# SparkFun_Beefcake_Relay_Control_Kit.net
KiCad netlist of a schematic drawn in EAGLE
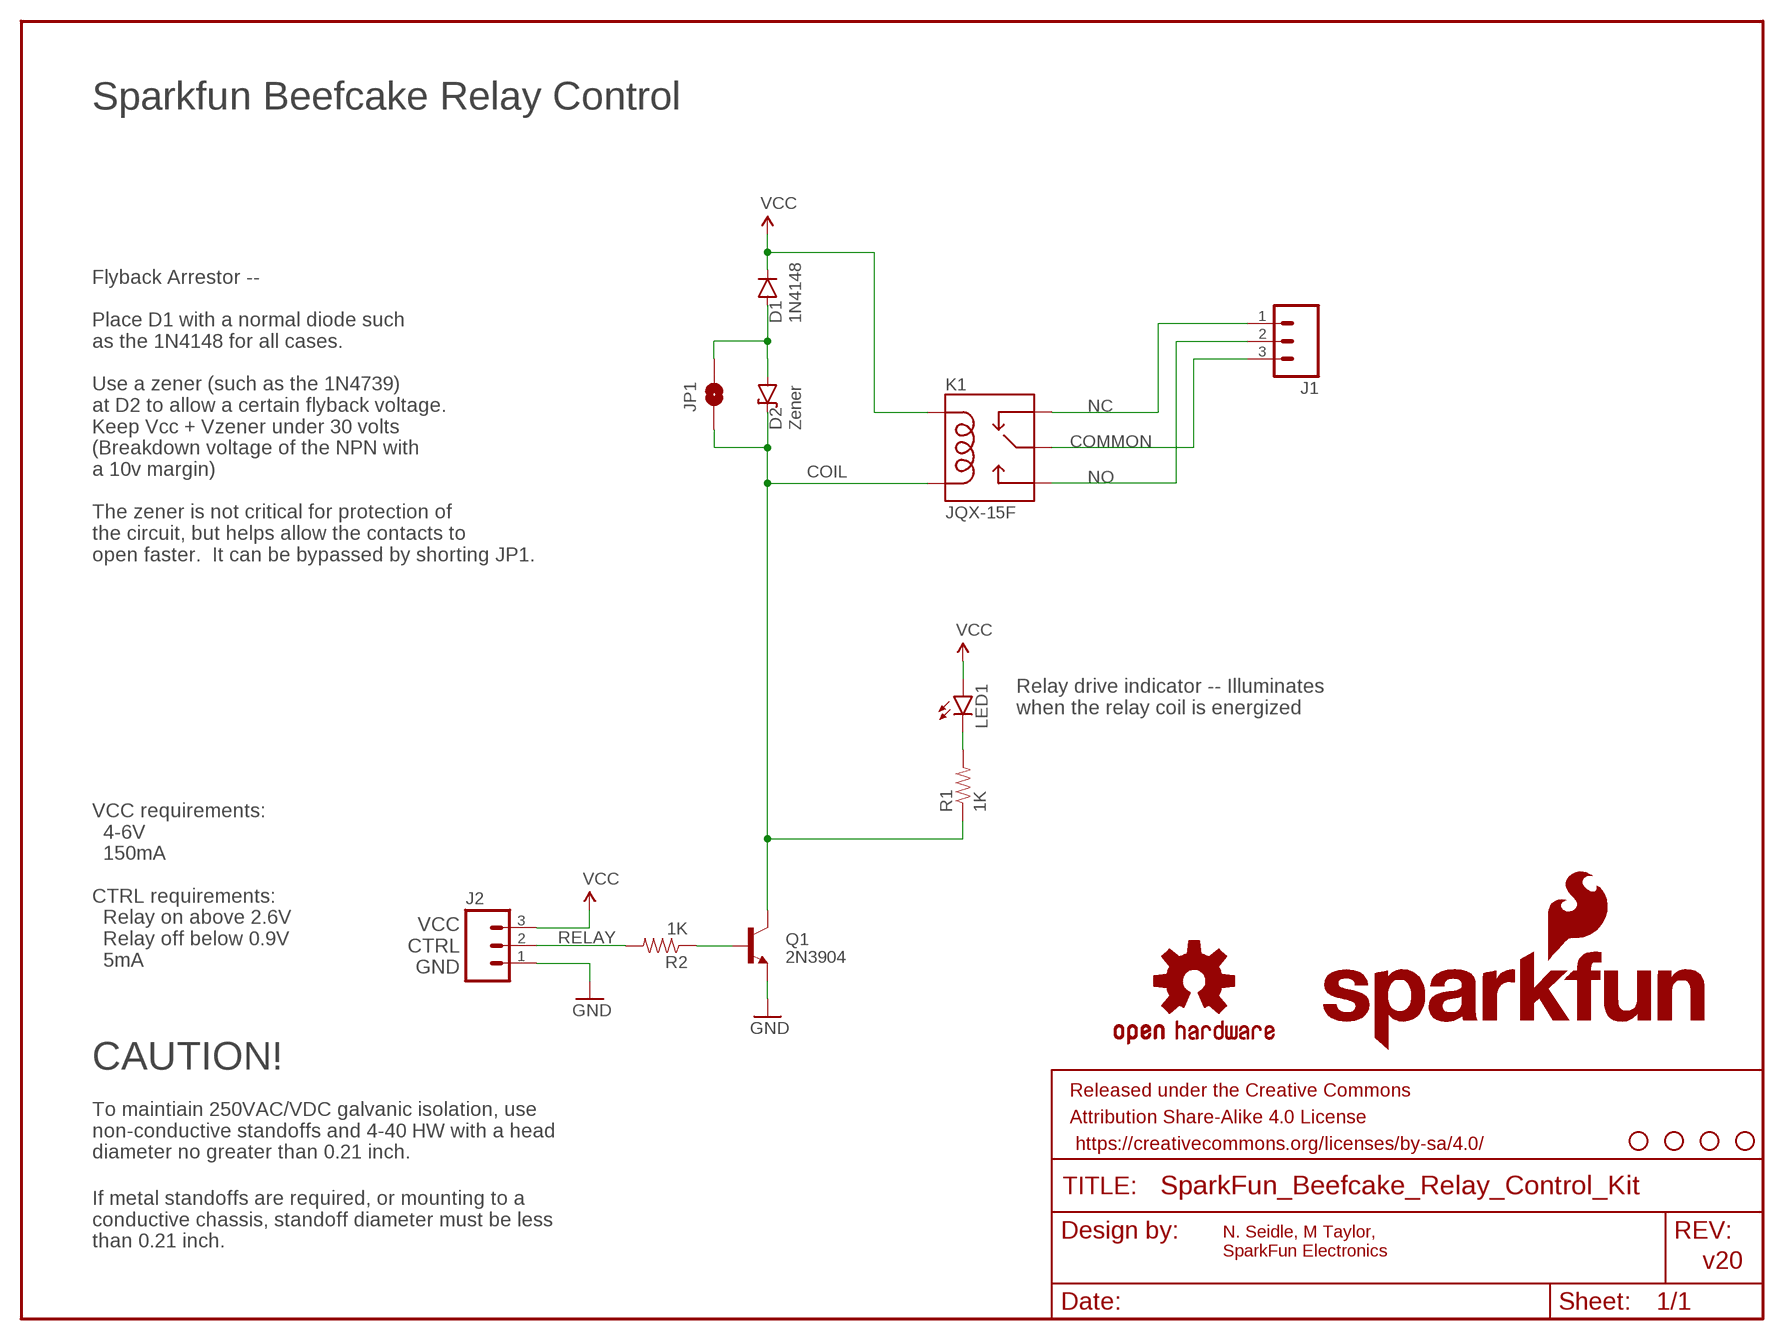
[diagram p0: schematic, sheet 1]

(export (version "E")
  (design (tool "Eeschema 10.0.6"))
  (components
    (comp (ref "D1")
      (value "1N4148")
      (footprint "eagle-import:DIODE-1N4148-KIT")
      (libsource (lib "eagle-import") (part "DIODEKIT"))
    )
    (comp (ref "D2")
      (value "Zener")
      (footprint "eagle-import:DIODE-1N4148-KIT")
      (libsource (lib "eagle-import") (part "DIODE-ZENER"))
    )
    (comp (ref "FRAME2")
      (value "FRAME-LETTER")
      (footprint "eagle-import:CREATIVE_COMMONS")
      (libsource (lib "eagle-import") (part "FRAME-LETTER"))
    )
    (comp (ref "J1")
      (value "M03-SCREW-5MM")
      (footprint "eagle-import:SCREWTERMINAL-5MM-3")
      (libsource (lib "eagle-import") (part "M03-SCREW-5MM"))
    )
    (comp (ref "J2")
      (value "M03SCREW")
      (footprint "eagle-import:SCREWTERMINAL-3.5MM-3")
      (libsource (lib "eagle-import") (part "M03SCREW"))
    )
    (comp (ref "JP1")
      (value "JUMPER-PAD-2-NOYES_SILK")
      (footprint "eagle-import:PAD-JUMPER-2-NO_YES_SILK")
      (libsource (lib "eagle-import") (part "JUMPER-PAD-2-NOYES_SILK"))
    )
    (comp (ref "K1")
      (value "JQX-15F")
      (footprint "eagle-import:RELAY-T90")
      (libsource (lib "eagle-import") (part "RELAYPTH5"))
    )
    (comp (ref "LED1")
      (value "LED5MM-KIT")
      (footprint "eagle-import:LED5MM-KIT")
      (fields (field (name "PROD_ID") "DIO-09529"))
      (libsource (lib "eagle-import") (part "LED5MM-KIT"))
    )
    (comp (ref "LOGO1")
      (value "SFE_LOGO_NAME_FLAME.1_INCH")
      (footprint "eagle-import:SFE_LOGO_NAME_FLAME_.1")
      (libsource (lib "eagle-import") (part "SFE_LOGO_NAME_FLAME.1_INCH"))
    )
    (comp (ref "Q1")
      (value "2N3904")
      (footprint "eagle-import:TO-92-EZ")
      (libsource (lib "eagle-import") (part "TRANSISTOR_NPN2N3904-EZ"))
    )
    (comp (ref "R1")
      (value "1K")
      (footprint "eagle-import:AXIAL-0.3EZ")
      (libsource (lib "eagle-import") (part "1KOHM-1/4W-1%(PTH)HORIZ-KIT"))
    )
    (comp (ref "R2")
      (value "1K")
      (footprint "eagle-import:AXIAL-0.3EZ")
      (libsource (lib "eagle-import") (part "1KOHM-1/4W-1%(PTH)HORIZ-KIT"))
    )
    (comp (ref "U$3")
      (value "STAND-OFF")
      (footprint "eagle-import:STAND-OFF")
      (libsource (lib "eagle-import") (part "STAND-OFF"))
    )
    (comp (ref "U$4")
      (value "STAND-OFF")
      (footprint "eagle-import:STAND-OFF")
      (libsource (lib "eagle-import") (part "STAND-OFF"))
    )
    (comp (ref "U$5")
      (value "STAND-OFF")
      (footprint "eagle-import:STAND-OFF")
      (libsource (lib "eagle-import") (part "STAND-OFF"))
    )
    (comp (ref "U$7")
      (value "STAND-OFF")
      (footprint "eagle-import:STAND-OFF")
      (libsource (lib "eagle-import") (part "STAND-OFF"))
    )
    (comp (ref "U$12")
      (value "OSHW-LOGOS")
      (footprint "eagle-import:OSHW-LOGO-S")
      (libsource (lib "eagle-import") (part "OSHW-LOGOS"))
    )
  )
  (nets
    (net (code "1") (name "/COIL") (class "Default")
      (node (ref "D2") (pin "C") (pinfunction "C_C") (pintype "passive"))
      (node (ref "JP1") (pin "1") (pinfunction "1_1") (pintype "passive"))
      (node (ref "K1") (pin "COIL2") (pinfunction "COIL2_COIL2") (pintype "bidirectional"))
      (node (ref "Q1") (pin "3") (pinfunction "C_3") (pintype "passive"))
      (node (ref "R1") (pin "P$1") (pinfunction "1_P$1") (pintype "passive"))
    )
    (net (code "2") (name "/COMMON") (class "Default")
      (node (ref "J1") (pin "3") (pinfunction "3_3") (pintype "passive"))
      (node (ref "K1") (pin "MAIN") (pinfunction "MAIN_MAIN") (pintype "bidirectional"))
    )
    (net (code "3") (name "/NC") (class "Default")
      (node (ref "J1") (pin "1") (pinfunction "1_1") (pintype "passive"))
      (node (ref "K1") (pin "NC") (pinfunction "NC_NC") (pintype "bidirectional"))
    )
    (net (code "4") (name "/NO") (class "Default")
      (node (ref "J1") (pin "2") (pinfunction "2_2") (pintype "passive"))
      (node (ref "K1") (pin "NO") (pinfunction "NO_NO") (pintype "bidirectional"))
    )
    (net (code "5") (name "/RELAY") (class "Default")
      (node (ref "J2") (pin "2") (pinfunction "2_2") (pintype "passive"))
      (node (ref "R2") (pin "P$2") (pinfunction "2_P$2") (pintype "passive"))
    )
    (net (code "6") (name "GND") (class "Default")
      (node (ref "J2") (pin "1") (pinfunction "1_1") (pintype "passive"))
      (node (ref "Q1") (pin "1") (pinfunction "E_1") (pintype "passive"))
    )
    (net (code "7") (name "Net-(D1-PadA)") (class "Default")
      (node (ref "D1") (pin "A") (pinfunction "A_A") (pintype "passive"))
      (node (ref "D2") (pin "A") (pinfunction "A_A") (pintype "passive"))
      (node (ref "JP1") (pin "2") (pinfunction "2_2") (pintype "passive"))
    )
    (net (code "8") (name "Net-(LED1-C)") (class "Default")
      (node (ref "LED1") (pin "K") (pinfunction "C_K") (pintype "passive"))
      (node (ref "R1") (pin "P$2") (pinfunction "2_P$2") (pintype "passive"))
    )
    (net (code "9") (name "Net-(Q1-B)") (class "Default")
      (node (ref "Q1") (pin "2") (pinfunction "B_2") (pintype "passive"))
      (node (ref "R2") (pin "P$1") (pinfunction "1_P$1") (pintype "passive"))
    )
    (net (code "10") (name "VCC") (class "Default")
      (node (ref "D1") (pin "C") (pinfunction "C_C") (pintype "passive"))
      (node (ref "J2") (pin "3") (pinfunction "3_3") (pintype "passive"))
      (node (ref "K1") (pin "COIL1") (pinfunction "COIL1_COIL1") (pintype "bidirectional"))
      (node (ref "LED1") (pin "A") (pinfunction "A_A") (pintype "passive"))
    )
  )
)
